# button.net
KiCad netlist of a schematic drawn in Altium Designer
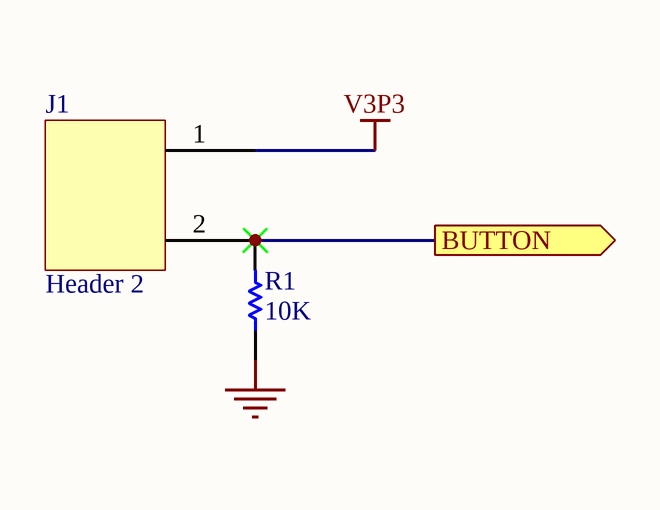
[diagram p0: button.SchDoc]

(export (version "E")
  (design (tool "Eeschema 10.0.6"))
  (components
    (comp (ref "J1")
      (value "Header 2")
      (footprint "Header 2 BUTTON")
      (libsource (lib "Klotz") (part "Header 2"))
    )
    (comp (ref "R1")
      (value "10K")
      (footprint "Resistor")
      (description "Resistor")
      (fields (field (name "PUBLISHER") "Altium Limited"))
      (libsource (lib "Miscellaneous Devices") (part "Res1"))
    )
  )
  (nets
    (net (code "1") (name "/BUTTON") (class "Default")
      (node (ref "J1") (pin "2") (pintype "power_in"))
      (node (ref "R1") (pin "2") (pinfunction "2_2") (pintype "passive"))
    )
    (net (code "2") (name "GND") (class "Default")
      (node (ref "R1") (pin "1") (pinfunction "1_1") (pintype "passive"))
    )
    (net (code "3") (name "V3P3") (class "Default") (node (ref "J1") (pin "1") (pintype "power_in")))
  )
)
